# micamp.net
KiCad netlist of a schematic drawn in EAGLE
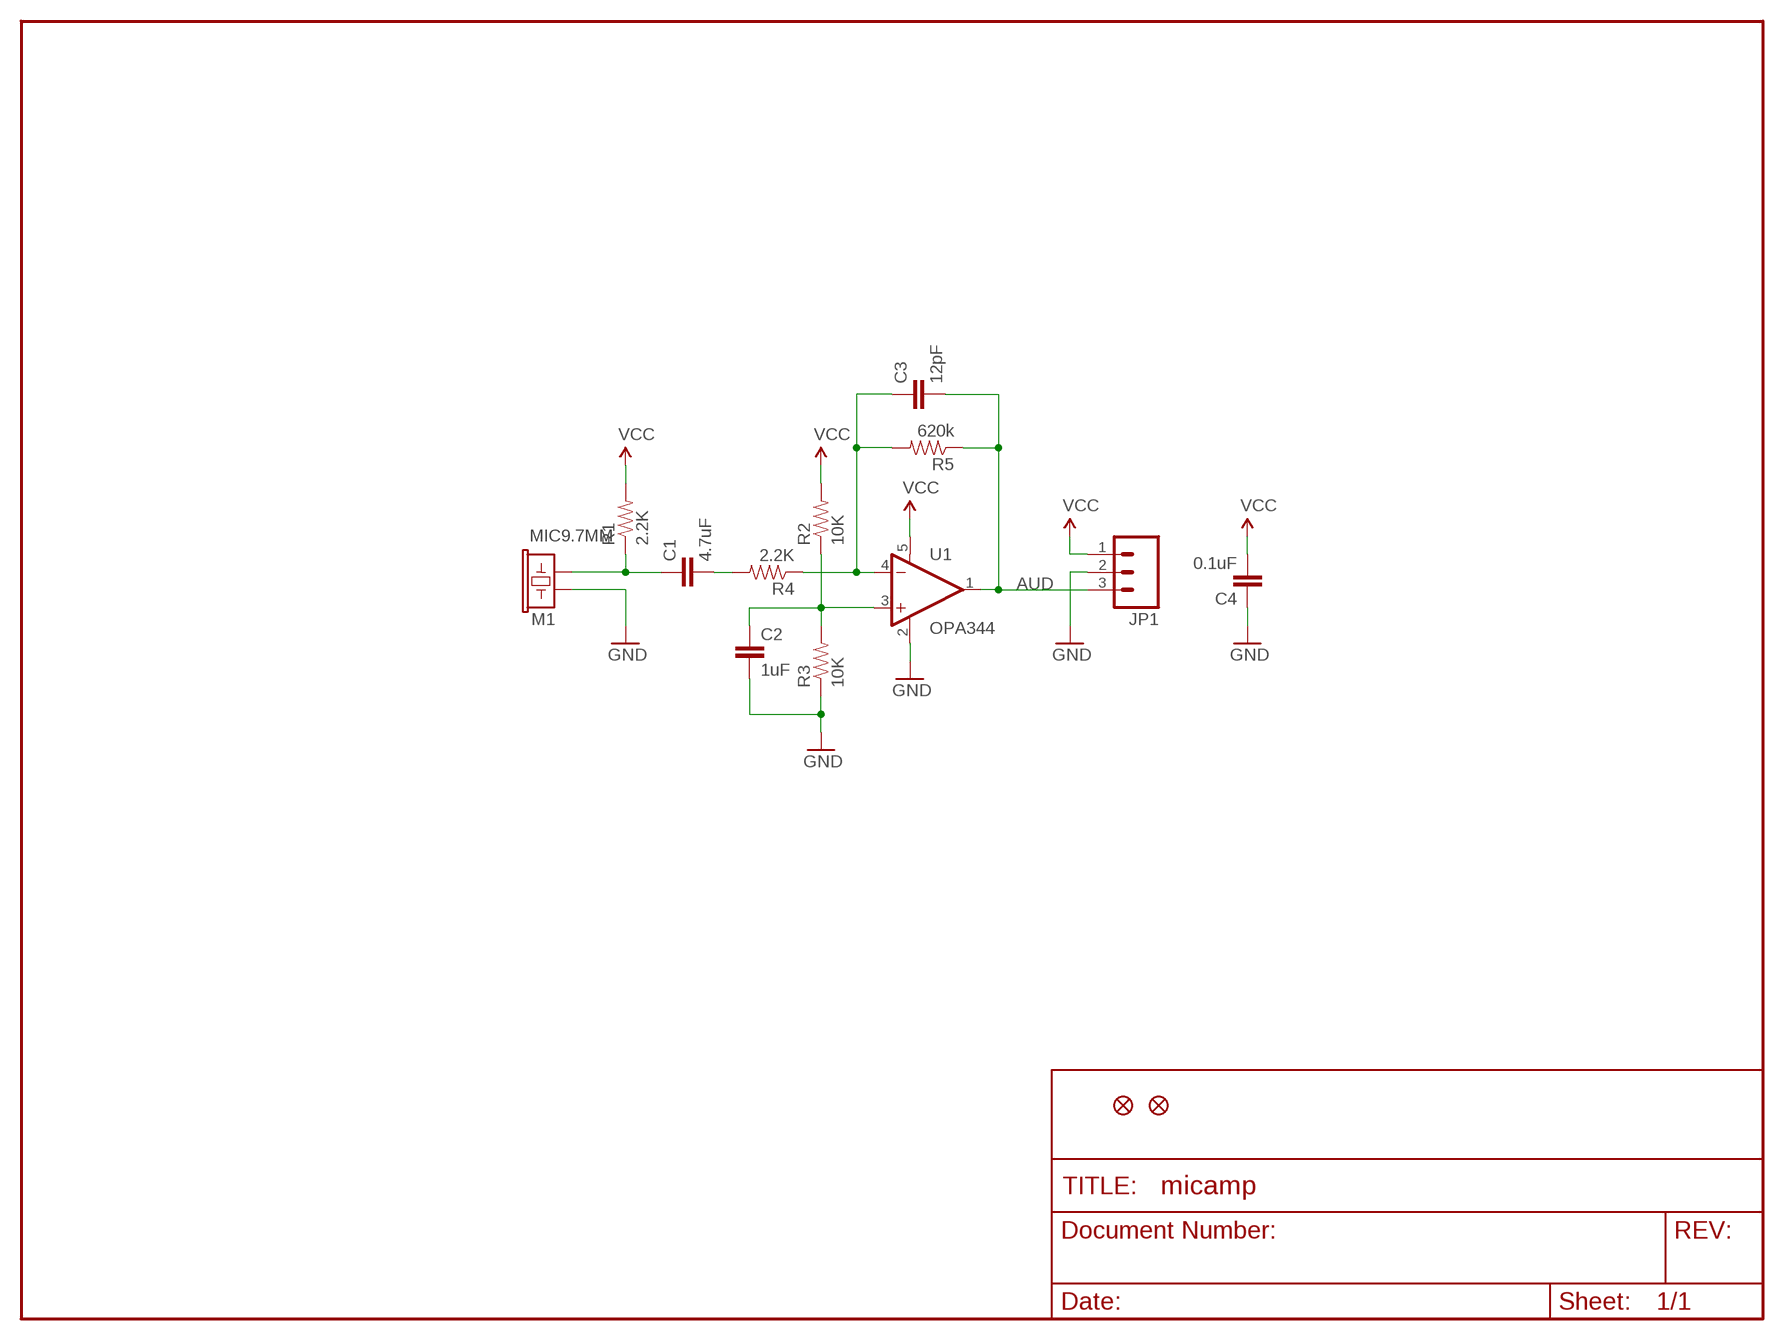
[diagram p0: schematic, sheet 1]

(export (version "E")
  (design (tool "Eeschema 10.0.6"))
  (components
    (comp (ref "C1")
      (value "4.7uF")
      (footprint "eagle-import:0603-CAP")
      (libsource (lib "eagle-import") (part "CAP0603-CAP"))
    )
    (comp (ref "C2")
      (value "1uF")
      (footprint "eagle-import:0603-CAP")
      (libsource (lib "eagle-import") (part "CAP0603-CAP"))
    )
    (comp (ref "C3")
      (value "12pF")
      (footprint "eagle-import:0603-CAP")
      (libsource (lib "eagle-import") (part "CAP0603-CAP"))
    )
    (comp (ref "C4")
      (value "0.1uF")
      (footprint "eagle-import:0603-CAP")
      (libsource (lib "eagle-import") (part "CAP0603-CAP"))
    )
    (comp (ref "JP1")
      (value "M03PTH")
      (footprint "eagle-import:1X03")
      (libsource (lib "eagle-import") (part "M03PTH"))
    )
    (comp (ref "JP2")
      (value "FIDUCIAL1X2")
      (footprint "eagle-import:FIDUCIAL-1X2")
      (libsource (lib "eagle-import") (part "FIDUCIAL1X2"))
    )
    (comp (ref "JP3")
      (value "FIDUCIAL1X2")
      (footprint "eagle-import:FIDUCIAL-1X2")
      (libsource (lib "eagle-import") (part "FIDUCIAL1X2"))
    )
    (comp (ref "M1")
      (value "MIC9.7MM")
      (footprint "eagle-import:MIC-9.7MM")
      (libsource (lib "eagle-import") (part "MIC9.7MM"))
    )
    (comp (ref "R1")
      (value "2.2K")
      (footprint "eagle-import:0603-RES")
      (libsource (lib "eagle-import") (part "RESISTOR0603-RES"))
    )
    (comp (ref "R2")
      (value "10K")
      (footprint "eagle-import:0603-RES")
      (libsource (lib "eagle-import") (part "RESISTOR0603-RES"))
    )
    (comp (ref "R3")
      (value "10K")
      (footprint "eagle-import:0603-RES")
      (libsource (lib "eagle-import") (part "RESISTOR0603-RES"))
    )
    (comp (ref "R4")
      (value "2.2K")
      (footprint "eagle-import:0603-RES")
      (libsource (lib "eagle-import") (part "RESISTOR0603-RES"))
    )
    (comp (ref "R5")
      (value "620k")
      (footprint "eagle-import:0603-RES")
      (libsource (lib "eagle-import") (part "RESISTOR0603-RES"))
    )
    (comp (ref "U1")
      (value "OPA344")
      (footprint "eagle-import:SOT23-5")
      (libsource (lib "eagle-import") (part "OPA344"))
    )
  )
  (nets
    (net (code "1") (name "/AUD") (class "Default")
      (node (ref "C3") (pin "2") (pinfunction "2_2") (pintype "passive"))
      (node (ref "JP1") (pin "3") (pinfunction "3_3") (pintype "passive"))
      (node (ref "R5") (pin "1") (pinfunction "1_1") (pintype "passive"))
      (node (ref "U1") (pin "1") (pinfunction "OUT_1") (pintype "output"))
    )
    (net (code "2") (name "GND") (class "Default")
      (node (ref "C2") (pin "2") (pinfunction "2_2") (pintype "passive"))
      (node (ref "C4") (pin "1") (pinfunction "1_1") (pintype "passive"))
      (node (ref "JP1") (pin "2") (pinfunction "2_2") (pintype "passive"))
      (node (ref "M1") (pin "2") (pinfunction "2_2") (pintype "passive"))
      (node (ref "R3") (pin "1") (pinfunction "1_1") (pintype "passive"))
      (node (ref "U1") (pin "2") (pinfunction "V-_2") (pintype "power_in"))
    )
    (net (code "3") (name "Net-(C1-Pad1)") (class "Default")
      (node (ref "C1") (pin "1") (pinfunction "1_1") (pintype "passive"))
      (node (ref "M1") (pin "1") (pinfunction "1_1") (pintype "passive"))
      (node (ref "R1") (pin "1") (pinfunction "1_1") (pintype "passive"))
    )
    (net (code "4") (name "Net-(C1-Pad2)") (class "Default")
      (node (ref "C1") (pin "2") (pinfunction "2_2") (pintype "passive"))
      (node (ref "R4") (pin "2") (pinfunction "2_2") (pintype "passive"))
    )
    (net (code "5") (name "Net-(U1-+IN)") (class "Default")
      (node (ref "C2") (pin "1") (pinfunction "1_1") (pintype "passive"))
      (node (ref "R2") (pin "1") (pinfunction "1_1") (pintype "passive"))
      (node (ref "R3") (pin "2") (pinfunction "2_2") (pintype "passive"))
      (node (ref "U1") (pin "3") (pinfunction "+IN_3") (pintype "input"))
    )
    (net (code "6") (name "Net-(U1--IN)") (class "Default")
      (node (ref "C3") (pin "1") (pinfunction "1_1") (pintype "passive"))
      (node (ref "R4") (pin "1") (pinfunction "1_1") (pintype "passive"))
      (node (ref "R5") (pin "2") (pinfunction "2_2") (pintype "passive"))
      (node (ref "U1") (pin "4") (pinfunction "-IN_4") (pintype "input"))
    )
    (net (code "7") (name "VCC") (class "Default")
      (node (ref "C4") (pin "2") (pinfunction "2_2") (pintype "passive"))
      (node (ref "JP1") (pin "1") (pinfunction "1_1") (pintype "passive"))
      (node (ref "R1") (pin "2") (pinfunction "2_2") (pintype "passive"))
      (node (ref "R2") (pin "2") (pinfunction "2_2") (pintype "passive"))
      (node (ref "U1") (pin "5") (pinfunction "V+_5") (pintype "power_in"))
    )
  )
)
